# Receiver_Can_Control_Module_Teensy_Rev2.net
KiCad netlist of a schematic drawn in EAGLE
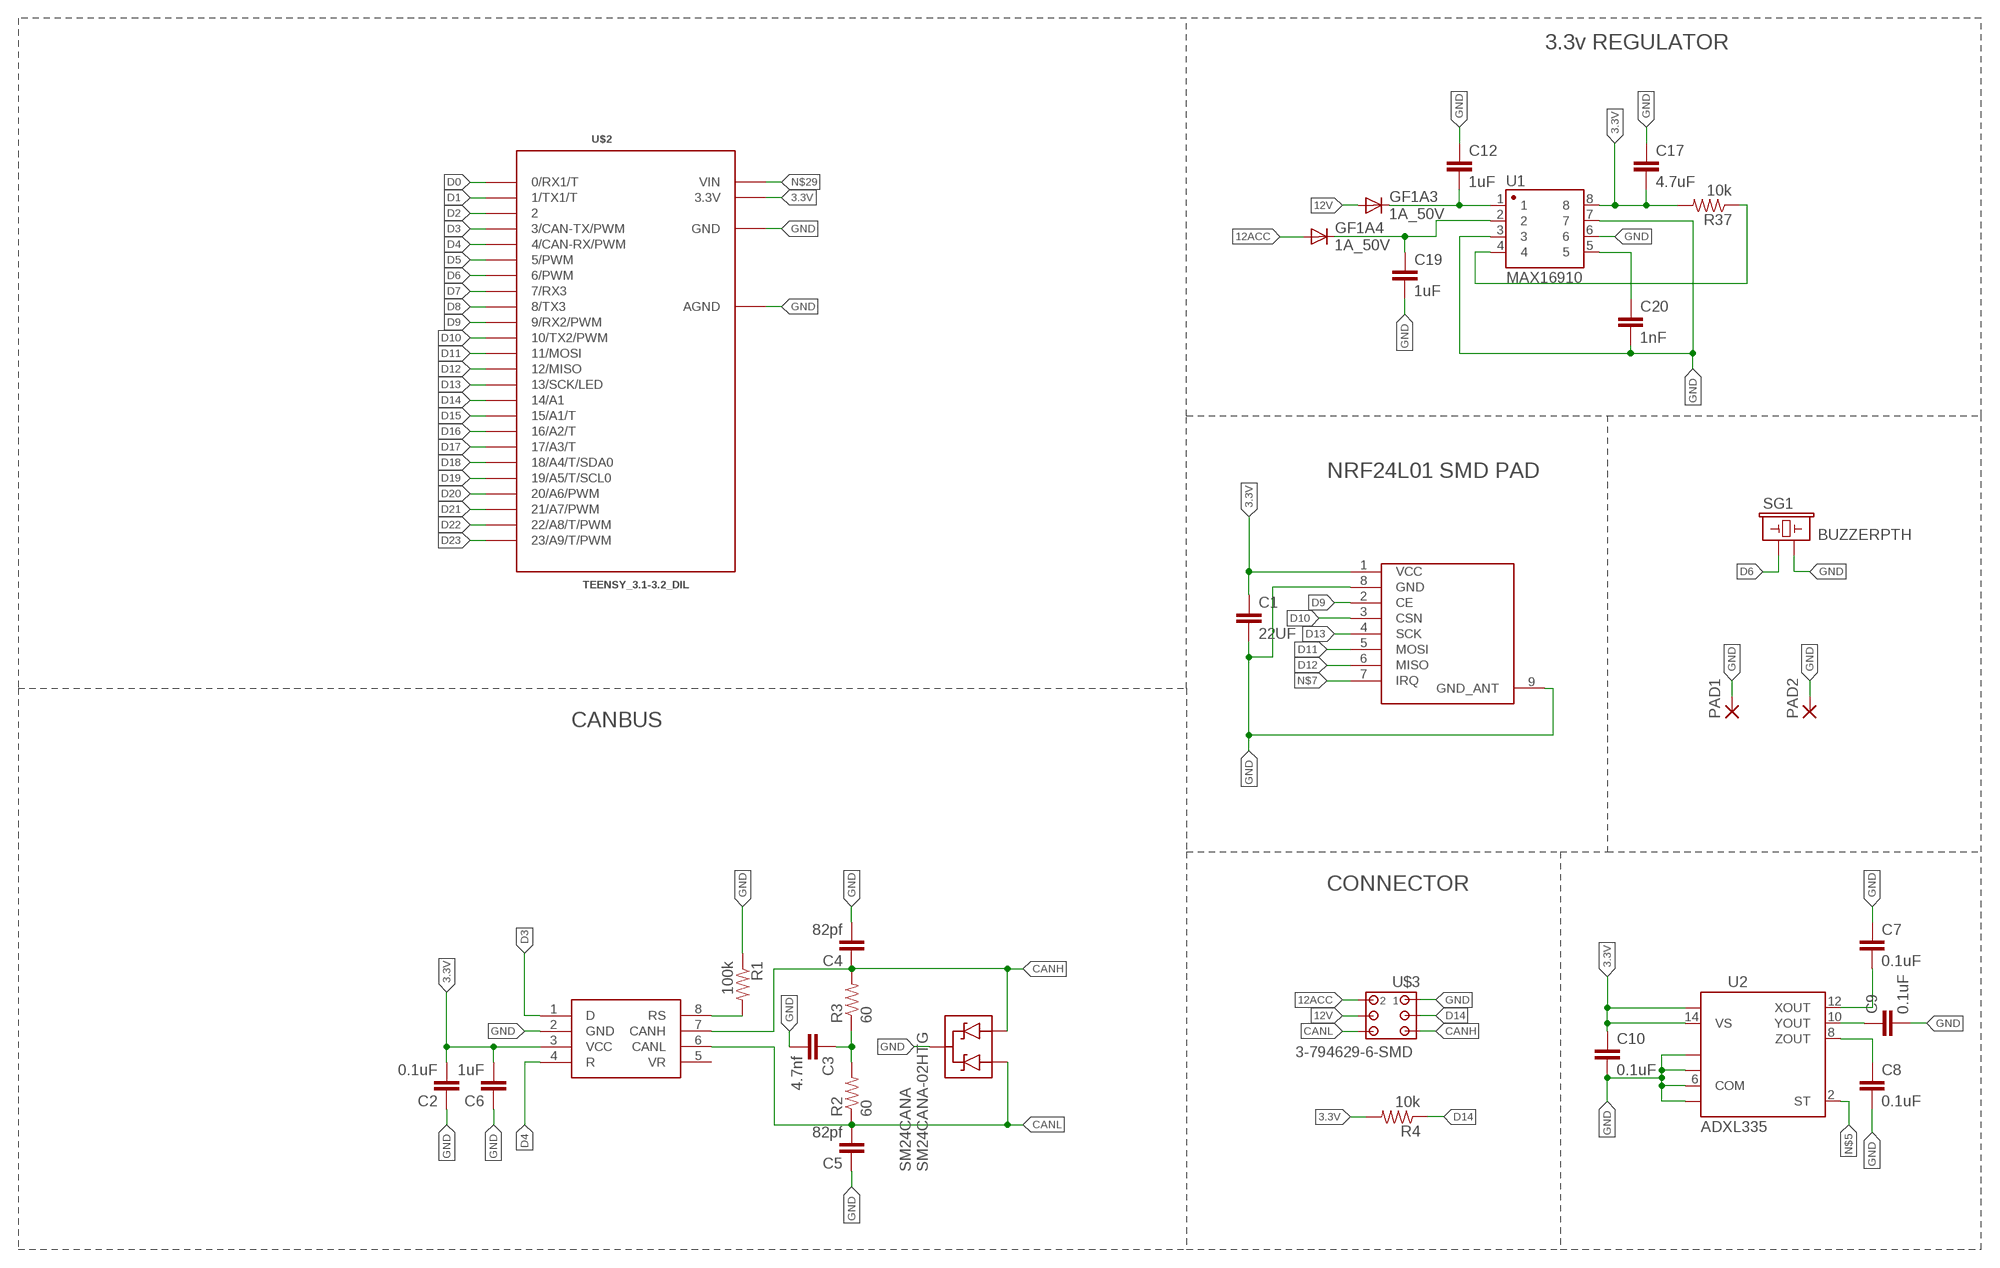
[diagram p0: schematic, sheet 1]

(export (version "E")
  (design (tool "Eeschema 10.0.6"))
  (components
    (comp (ref "C1")
      (value "22UF")
      (footprint "eagle-import:1206")
      (libsource (lib "eagle-import") (part "CAP1206"))
    )
    (comp (ref "C2")
      (value "0.1uF")
      (footprint "eagle-import:0603-CAP")
      (libsource (lib "eagle-import") (part "SparkFun-Capacitors_CAP0603-CAP"))
    )
    (comp (ref "C3")
      (value "4.7nf")
      (footprint "eagle-import:0603-CAP")
      (libsource (lib "eagle-import") (part "SparkFun-Capacitors_CAP0603-CAP"))
    )
    (comp (ref "C4")
      (value "82pf")
      (footprint "eagle-import:0603-CAP")
      (libsource (lib "eagle-import") (part "SparkFun-Capacitors_CAP0603-CAP"))
    )
    (comp (ref "C5")
      (value "82pf")
      (footprint "eagle-import:0603-CAP")
      (libsource (lib "eagle-import") (part "SparkFun-Capacitors_CAP0603-CAP"))
    )
    (comp (ref "C6")
      (value "1uF")
      (footprint "eagle-import:0603-CAP")
      (libsource (lib "eagle-import") (part "SparkFun-Capacitors_CAP0603-CAP"))
    )
    (comp (ref "C7")
      (value "0.1uF")
      (footprint "eagle-import:0603-CAP")
      (libsource (lib "eagle-import") (part "SparkFun-Capacitors_CAP0603-CAP"))
    )
    (comp (ref "C8")
      (value "0.1uF")
      (footprint "eagle-import:0603-CAP")
      (libsource (lib "eagle-import") (part "SparkFun-Capacitors_CAP0603-CAP"))
    )
    (comp (ref "C9")
      (value "0.1uF")
      (footprint "eagle-import:0603-CAP")
      (libsource (lib "eagle-import") (part "SparkFun-Capacitors_CAP0603-CAP"))
    )
    (comp (ref "C10")
      (value "0.1uF")
      (footprint "eagle-import:0603-CAP")
      (libsource (lib "eagle-import") (part "SparkFun-Capacitors_CAP0603-CAP"))
    )
    (comp (ref "C12")
      (value "1uF")
      (footprint "eagle-import:0805")
      (libsource (lib "eagle-import") (part "SparkFun-Capacitors_CAP0805"))
    )
    (comp (ref "C17")
      (value "4.7uF")
      (footprint "eagle-import:0805")
      (libsource (lib "eagle-import") (part "SparkFun-Capacitors_CAP0805"))
    )
    (comp (ref "C19")
      (value "1uF")
      (footprint "eagle-import:0805")
      (libsource (lib "eagle-import") (part "SparkFun-Capacitors_CAP0805"))
    )
    (comp (ref "C20")
      (value "1nF")
      (footprint "eagle-import:0805")
      (libsource (lib "eagle-import") (part "SparkFun-Capacitors_CAP0805"))
    )
    (comp (ref "GF1A3")
      (value "1A_50V")
      (footprint "eagle-import:DO-214AC")
      (libsource (lib "eagle-import") (part "DIODE-DO-214AC"))
    )
    (comp (ref "GF1A4")
      (value "1A_50V")
      (footprint "eagle-import:DO-214AC")
      (libsource (lib "eagle-import") (part "DIODE-DO-214AC"))
    )
    (comp (ref "PAD1")
      (value "SMD2")
      (footprint "eagle-import:SMD1,27-2,54")
      (libsource (lib "eagle-import") (part "SMD2"))
    )
    (comp (ref "PAD2")
      (value "SMD2")
      (footprint "eagle-import:SMD1,27-2,54")
      (libsource (lib "eagle-import") (part "SMD2"))
    )
    (comp (ref "R1")
      (value "100k")
      (footprint "eagle-import:R0402")
      (libsource (lib "eagle-import") (part "R-US_R0402"))
    )
    (comp (ref "R2")
      (value "60")
      (footprint "eagle-import:R0402")
      (libsource (lib "eagle-import") (part "R-US_R0402"))
    )
    (comp (ref "R3")
      (value "60")
      (footprint "eagle-import:R0402")
      (libsource (lib "eagle-import") (part "R-US_R0402"))
    )
    (comp (ref "R4")
      (value "10k")
      (footprint "eagle-import:0603-RES")
      (libsource (lib "eagle-import") (part "RESISTOR0603-RES"))
    )
    (comp (ref "R37")
      (value "10k")
      (footprint "eagle-import:0603-RES")
      (libsource (lib "eagle-import") (part "RESISTOR0603-RES"))
    )
    (comp (ref "SG1")
      (value "BUZZERPTH")
      (footprint "eagle-import:BUZZER-12MM")
      (libsource (lib "eagle-import") (part "BUZZERPTH"))
    )
    (comp (ref "SM24CANA")
      (value "SM24CANA-02HTG")
      (footprint "eagle-import:SOT23-3")
      (libsource (lib "eagle-import") (part "MMBZ27VCLT1"))
    )
    (comp (ref "U$1")
      (value "NRF24L01_PAD2")
      (footprint "eagle-import:NRF24-2")
      (libsource (lib "eagle-import") (part "NRF24L01_PAD2"))
    )
    (comp (ref "U$2")
      (value "TEENSY_3.1-3.2_DIL")
      (footprint "eagle-import:TEENSY_3.0-3.2&LC_DIL")
      (libsource (lib "eagle-import") (part "TEENSY_3.1-3.2_DIL"))
    )
    (comp (ref "U$3")
      (value "3-794629-6-SMD")
      (footprint "eagle-import:3-794629-6")
      (libsource (lib "eagle-import") (part "3-794629-6-SMD"))
    )
    (comp (ref "U1")
      (value "MAX16910")
      (footprint "eagle-import:SO08")
      (libsource (lib "eagle-import") (part "GENERIC-SOIC8MSGEQ7N-FILTER"))
    )
    (comp (ref "U2")
      (value "ADXL335")
      (footprint "eagle-import:LFCSP-16")
      (libsource (lib "eagle-import") (part "ADXL335"))
    )
    (comp (ref "VP230")
      (value "UP230")
      (footprint "eagle-import:SO08")
      (libsource (lib "eagle-import") (part "SN65HVD230"))
    )
  )
  (nets
    (net (code "1") (name "3.3V") (class "Default")
      (node (ref "C1") (pin "1") (pinfunction "1_1") (pintype "passive"))
      (node (ref "C10") (pin "1") (pinfunction "1_1") (pintype "passive"))
      (node (ref "C17") (pin "2") (pinfunction "2_2") (pintype "passive"))
      (node (ref "C2") (pin "2") (pinfunction "2_2") (pintype "passive"))
      (node (ref "C6") (pin "2") (pinfunction "2_2") (pintype "passive"))
      (node (ref "R37") (pin "2") (pinfunction "2_2") (pintype "passive"))
      (node (ref "R4") (pin "2") (pinfunction "2_2") (pintype "passive"))
      (node (ref "U$1") (pin "1") (pinfunction "VCC_1") (pintype "bidirectional"))
      (node (ref "U$2") (pin "3.3V") (pinfunction "3.3V_3.3V") (pintype "power_in"))
      (node (ref "U1") (pin "8") (pinfunction "8_8") (pintype "bidirectional"))
      (node (ref "U2") (pin "14") (pinfunction "VS_14") (pintype "bidirectional"))
      (node (ref "U2") (pin "15") (pinfunction "VS_15") (pintype "bidirectional"))
      (node (ref "VP230") (pin "3") (pinfunction "VCC_3") (pintype "bidirectional"))
    )
    (net (code "2") (name "12ACC") (class "Default")
      (node (ref "GF1A4") (pin "A") (pinfunction "A_A") (pintype "passive"))
      (node (ref "U$3") (pin "2") (pinfunction "2_2") (pintype "passive"))
    )
    (net (code "3") (name "12V") (class "Default")
      (node (ref "GF1A3") (pin "A") (pinfunction "A_A") (pintype "passive"))
      (node (ref "U$3") (pin "4") (pinfunction "4_4") (pintype "passive"))
    )
    (net (code "4") (name "CANH") (class "Default")
      (node (ref "C4") (pin "1") (pinfunction "1_1") (pintype "passive"))
      (node (ref "R3") (pin "2") (pinfunction "2_2") (pintype "passive"))
      (node (ref "SM24CANA") (pin "2") (pinfunction "A2_2") (pintype "passive"))
      (node (ref "U$3") (pin "5") (pinfunction "5_5") (pintype "passive"))
      (node (ref "VP230") (pin "7") (pinfunction "CANH_7") (pintype "bidirectional"))
    )
    (net (code "5") (name "CANL") (class "Default")
      (node (ref "C5") (pin "2") (pinfunction "2_2") (pintype "passive"))
      (node (ref "R2") (pin "1") (pinfunction "1_1") (pintype "passive"))
      (node (ref "SM24CANA") (pin "1") (pinfunction "A1_1") (pintype "passive"))
      (node (ref "U$3") (pin "6") (pinfunction "6_6") (pintype "passive"))
      (node (ref "VP230") (pin "6") (pinfunction "CANL_6") (pintype "bidirectional"))
    )
    (net (code "6") (name "D0") (class "Default")
      (node (ref "U$2") (pin "0") (pinfunction "0/RX1/T_0") (pintype "bidirectional"))
    )
    (net (code "7") (name "D1") (class "Default")
      (node (ref "U$2") (pin "1") (pinfunction "1/TX1/T_1") (pintype "bidirectional"))
    )
    (net (code "8") (name "D2") (class "Default")
      (node (ref "U$2") (pin "2") (pinfunction "2_2") (pintype "bidirectional"))
    )
    (net (code "9") (name "D3") (class "Default")
      (node (ref "U$2") (pin "3") (pinfunction "3/CAN-TX/PWM_3") (pintype "bidirectional"))
      (node (ref "VP230") (pin "1") (pinfunction "D_1") (pintype "bidirectional"))
    )
    (net (code "10") (name "D4") (class "Default")
      (node (ref "U$2") (pin "4") (pinfunction "4/CAN-RX/PWM_4") (pintype "bidirectional"))
      (node (ref "VP230") (pin "4") (pinfunction "R_4") (pintype "bidirectional"))
    )
    (net (code "11") (name "D5") (class "Default")
      (node (ref "U$2") (pin "5") (pinfunction "5/PWM_5") (pintype "bidirectional"))
    )
    (net (code "12") (name "D6") (class "Default")
      (node (ref "SG1") (pin "+") (pinfunction "1_+") (pintype "passive"))
      (node (ref "U$2") (pin "6") (pinfunction "6/PWM_6") (pintype "bidirectional"))
    )
    (net (code "13") (name "D7") (class "Default")
      (node (ref "U$2") (pin "7") (pinfunction "7/RX3_7") (pintype "bidirectional"))
    )
    (net (code "14") (name "D8") (class "Default")
      (node (ref "U$2") (pin "8") (pinfunction "8/TX3_8") (pintype "bidirectional"))
    )
    (net (code "15") (name "D9") (class "Default")
      (node (ref "U$1") (pin "2") (pinfunction "CE_2") (pintype "bidirectional"))
      (node (ref "U$2") (pin "9") (pinfunction "9/RX2/PWM_9") (pintype "bidirectional"))
    )
    (net (code "16") (name "D10") (class "Default")
      (node (ref "U$1") (pin "3") (pinfunction "CSN_3") (pintype "bidirectional"))
      (node (ref "U$2") (pin "10") (pinfunction "10/TX2/PWM_10") (pintype "bidirectional"))
    )
    (net (code "17") (name "D11") (class "Default")
      (node (ref "U$1") (pin "5") (pinfunction "MOSI_5") (pintype "bidirectional"))
      (node (ref "U$2") (pin "11") (pinfunction "11/MOSI_11") (pintype "bidirectional"))
    )
    (net (code "18") (name "D12") (class "Default")
      (node (ref "U$1") (pin "6") (pinfunction "MISO_6") (pintype "bidirectional"))
      (node (ref "U$2") (pin "12") (pinfunction "12/MISO_12") (pintype "bidirectional"))
    )
    (net (code "19") (name "D13") (class "Default")
      (node (ref "U$1") (pin "4") (pinfunction "SCK_4") (pintype "bidirectional"))
      (node (ref "U$2") (pin "13") (pinfunction "13/SCK/LED_13") (pintype "bidirectional"))
    )
    (net (code "20") (name "D14") (class "Default")
      (node (ref "R4") (pin "1") (pinfunction "1_1") (pintype "passive"))
      (node (ref "U$2") (pin "14/A0") (pinfunction "14/A1_14/A0") (pintype "bidirectional"))
      (node (ref "U$3") (pin "3") (pinfunction "3_3") (pintype "passive"))
    )
    (net (code "21") (name "D15") (class "Default")
      (node (ref "U$2") (pin "15/A1") (pinfunction "15/A1/T_15/A1") (pintype "bidirectional"))
    )
    (net (code "22") (name "D16") (class "Default")
      (node (ref "U$2") (pin "16/A2") (pinfunction "16/A2/T_16/A2") (pintype "bidirectional"))
    )
    (net (code "23") (name "D17") (class "Default")
      (node (ref "U$2") (pin "17/A3") (pinfunction "17/A3/T_17/A3") (pintype "bidirectional"))
    )
    (net (code "24") (name "D18") (class "Default")
      (node (ref "U$2") (pin "18/A4") (pinfunction "18/A4/T/SDA0_18/A4") (pintype "bidirectional"))
    )
    (net (code "25") (name "D19") (class "Default")
      (node (ref "U$2") (pin "19/A5") (pinfunction "19/A5/T/SCL0_19/A5") (pintype "bidirectional"))
    )
    (net (code "26") (name "D20") (class "Default")
      (node (ref "U$2") (pin "20/A6") (pinfunction "20/A6/PWM_20/A6") (pintype "bidirectional"))
    )
    (net (code "27") (name "D21") (class "Default")
      (node (ref "C7") (pin "2") (pinfunction "2_2") (pintype "passive"))
      (node (ref "U$2") (pin "21/A7") (pinfunction "21/A7/PWM_21/A7") (pintype "bidirectional"))
      (node (ref "U2") (pin "12") (pinfunction "XOUT_12") (pintype "bidirectional"))
    )
    (net (code "28") (name "D22") (class "Default")
      (node (ref "C9") (pin "1") (pinfunction "1_1") (pintype "passive"))
      (node (ref "U$2") (pin "22/A8") (pinfunction "22/A8/T/PWM_22/A8") (pintype "bidirectional"))
      (node (ref "U2") (pin "10") (pinfunction "YOUT_10") (pintype "bidirectional"))
    )
    (net (code "29") (name "D23") (class "Default")
      (node (ref "C8") (pin "1") (pinfunction "1_1") (pintype "passive"))
      (node (ref "U$2") (pin "23/A9") (pinfunction "23/A9/T/PWM_23/A9") (pintype "bidirectional"))
      (node (ref "U2") (pin "8") (pinfunction "ZOUT_8") (pintype "bidirectional"))
    )
    (net (code "30") (name "GND") (class "Default")
      (node (ref "C1") (pin "2") (pinfunction "2_2") (pintype "passive"))
      (node (ref "C10") (pin "2") (pinfunction "2_2") (pintype "passive"))
      (node (ref "C12") (pin "1") (pinfunction "1_1") (pintype "passive"))
      (node (ref "C17") (pin "1") (pinfunction "1_1") (pintype "passive"))
      (node (ref "C19") (pin "2") (pinfunction "2_2") (pintype "passive"))
      (node (ref "C2") (pin "1") (pinfunction "1_1") (pintype "passive"))
      (node (ref "C20") (pin "2") (pinfunction "2_2") (pintype "passive"))
      (node (ref "C3") (pin "2") (pinfunction "2_2") (pintype "passive"))
      (node (ref "C4") (pin "2") (pinfunction "2_2") (pintype "passive"))
      (node (ref "C5") (pin "1") (pinfunction "1_1") (pintype "passive"))
      (node (ref "C6") (pin "1") (pinfunction "1_1") (pintype "passive"))
      (node (ref "C7") (pin "1") (pinfunction "1_1") (pintype "passive"))
      (node (ref "C8") (pin "2") (pinfunction "2_2") (pintype "passive"))
      (node (ref "C9") (pin "2") (pinfunction "2_2") (pintype "passive"))
      (node (ref "PAD1") (pin "1") (pinfunction "P_1") (pintype "passive"))
      (node (ref "PAD2") (pin "1") (pinfunction "P_1") (pintype "passive"))
      (node (ref "R1") (pin "1") (pinfunction "1_1") (pintype "passive"))
      (node (ref "SG1") (pin "-") (pinfunction "2_-") (pintype "passive"))
      (node (ref "SM24CANA") (pin "3") (pinfunction "C_3") (pintype "passive"))
      (node (ref "U$1") (pin "8") (pinfunction "GND_8") (pintype "bidirectional"))
      (node (ref "U$1") (pin "9") (pinfunction "GND_ANT_9") (pintype "bidirectional"))
      (node (ref "U$2") (pin "AGND") (pinfunction "AGND_AGND") (pintype "power_in"))
      (node (ref "U$2") (pin "GND") (pinfunction "GND_GND") (pintype "power_in"))
      (node (ref "U$3") (pin "1") (pinfunction "1_1") (pintype "passive"))
      (node (ref "U1") (pin "3") (pinfunction "3_3") (pintype "bidirectional"))
      (node (ref "U1") (pin "6") (pinfunction "6_6") (pintype "bidirectional"))
      (node (ref "U1") (pin "7") (pinfunction "7_7") (pintype "bidirectional"))
      (node (ref "U2") (pin "3") (pinfunction "COM_3") (pintype "bidirectional"))
      (node (ref "U2") (pin "5") (pinfunction "COM_5") (pintype "bidirectional"))
      (node (ref "U2") (pin "6") (pinfunction "COM_6") (pintype "bidirectional"))
      (node (ref "U2") (pin "7") (pinfunction "COM_7") (pintype "bidirectional"))
      (node (ref "VP230") (pin "2") (pinfunction "GND_2") (pintype "bidirectional"))
    )
    (net (code "31") (name "N$5") (class "Default")
      (node (ref "U2") (pin "2") (pinfunction "ST_2") (pintype "bidirectional"))
    )
    (net (code "32") (name "N$7") (class "Default")
      (node (ref "U$1") (pin "7") (pinfunction "IRQ_7") (pintype "bidirectional"))
    )
    (net (code "33") (name "N$29") (class "Default")
      (node (ref "U$2") (pin "VIN") (pinfunction "VIN_VIN") (pintype "power_in"))
    )
    (net (code "34") (name "Net-(C3-Pad1)") (class "Default")
      (node (ref "C3") (pin "1") (pinfunction "1_1") (pintype "passive"))
      (node (ref "R2") (pin "2") (pinfunction "2_2") (pintype "passive"))
      (node (ref "R3") (pin "1") (pinfunction "1_1") (pintype "passive"))
    )
    (net (code "35") (name "Net-(C12-Pad2)") (class "Default")
      (node (ref "C12") (pin "2") (pinfunction "2_2") (pintype "passive"))
      (node (ref "GF1A3") (pin "C") (pinfunction "C_C") (pintype "passive"))
      (node (ref "U1") (pin "1") (pinfunction "1_1") (pintype "bidirectional"))
    )
    (net (code "36") (name "Net-(C19-Pad1)") (class "Default")
      (node (ref "C19") (pin "1") (pinfunction "1_1") (pintype "passive"))
      (node (ref "GF1A4") (pin "C") (pinfunction "C_C") (pintype "passive"))
      (node (ref "U1") (pin "2") (pinfunction "2_2") (pintype "bidirectional"))
    )
    (net (code "37") (name "Net-(C20-Pad1)") (class "Default")
      (node (ref "C20") (pin "1") (pinfunction "1_1") (pintype "passive"))
      (node (ref "U1") (pin "5") (pinfunction "5_5") (pintype "bidirectional"))
    )
    (net (code "38") (name "Net-(R37-Pad1)") (class "Default")
      (node (ref "R37") (pin "1") (pinfunction "1_1") (pintype "passive"))
      (node (ref "U1") (pin "4") (pinfunction "4_4") (pintype "bidirectional"))
    )
    (net (code "39") (name "Net-(VP230-RS)") (class "Default")
      (node (ref "R1") (pin "2") (pinfunction "2_2") (pintype "passive"))
      (node (ref "VP230") (pin "8") (pinfunction "RS_8") (pintype "bidirectional"))
    )
    (net (code "40") (name "unconnected-(VP230-VR-Pad5)") (class "Default")
      (node (ref "VP230") (pin "5") (pinfunction "VR_5") (pintype "bidirectional"))
    )
  )
)
